# BiSheB.net
KiCad netlist of a schematic drawn in Altium Designer
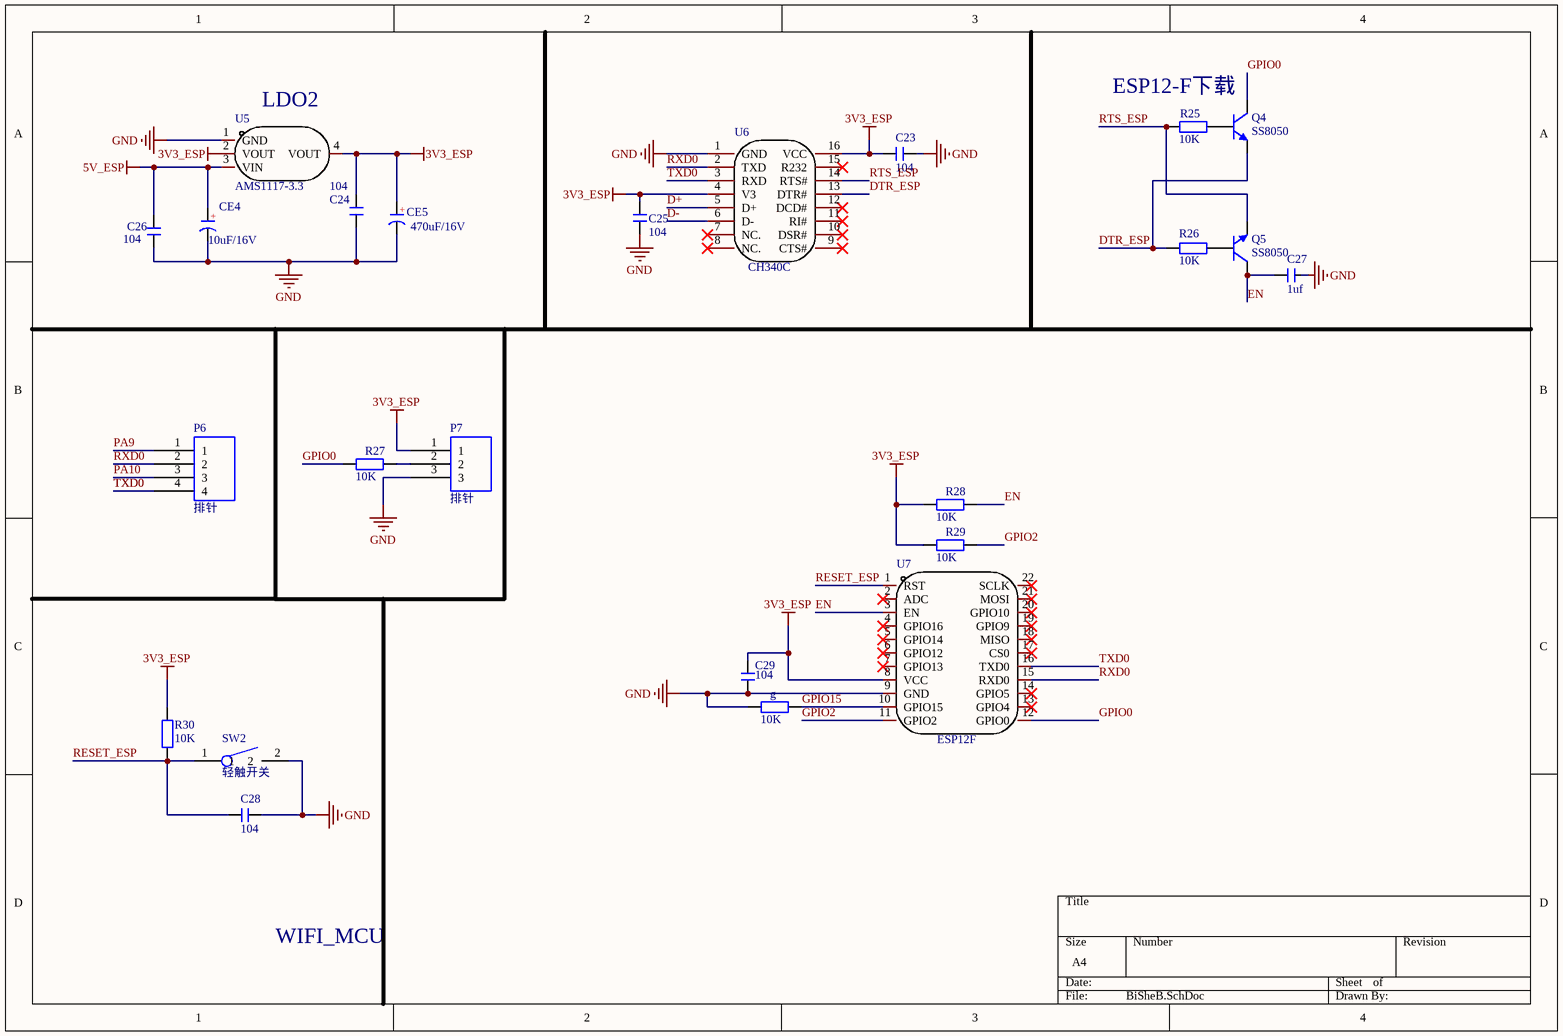
[diagram p0: BiSheB.SchDoc]

(export (version "E")
  (design (tool "Eeschema 10.0.6"))
  (components
    (comp (ref "C23")
      (value "104")
      (footprint "C 0805_L")
      (description "贴片电容")
      (libsource (lib "0.1 - 电阻-电容-电感") (part "C"))
    )
    (comp (ref "C24")
      (value "104")
      (footprint "C 0805_L")
      (description "贴片电容")
      (libsource (lib "0.1 - 电阻-电容-电感") (part "C"))
    )
    (comp (ref "C25")
      (value "104")
      (footprint "C 0805_L")
      (description "贴片电容")
      (libsource (lib "0.1 - 电阻-电容-电感") (part "C"))
    )
    (comp (ref "C26")
      (value "104")
      (footprint "C 0805_L")
      (description "贴片电容")
      (libsource (lib "0.1 - 电阻-电容-电感") (part "C"))
    )
    (comp (ref "C27")
      (value "1uf")
      (footprint "C 0805_L")
      (description "贴片电容")
      (libsource (lib "0.1 - 电阻-电容-电感") (part "C"))
    )
    (comp (ref "C28")
      (value "104")
      (footprint "C 0805_L")
      (description "贴片电容")
      (libsource (lib "0.1 - 电阻-电容-电感") (part "C"))
    )
    (comp (ref "C29")
      (value "104")
      (footprint "C 0805_L")
      (description "贴片电容")
      (libsource (lib "0.1 - 电阻-电容-电感") (part "C"))
    )
    (comp (ref "CE4")
      (value "10uF/16V")
      (footprint "CAP 1.5*4*8")
      (description "直插电解电容")
      (libsource (lib "0.1 - 电阻-电容-电感") (part "CE"))
    )
    (comp (ref "CE5")
      (value "470uF/16V")
      (footprint "CAP 3.5*8*11.5")
      (description "直插电解电容")
      (libsource (lib "0.1 - 电阻-电容-电感") (part "CE"))
    )
    (comp (ref "g")
      (value "10K")
      (footprint "R 0805_L")
      (description "贴片电阻")
      (fields (field (name "版权归属") "来自淘宝 ID：黄晶宝石"))
      (libsource (lib "0.1 - 电阻-电容-电感") (part "R"))
    )
    (comp (ref "P6")
      (value "排针")
      (footprint "4PIN")
      (description "4p排针")
      (libsource (lib "BiSheFinal") (part "4Pin"))
    )
    (comp (ref "P7")
      (value "排针")
      (footprint "3Pin")
      (description "3p排针")
      (libsource (lib "BiSheFinal") (part "3Pin"))
    )
    (comp (ref "Q4")
      (value "SS8050")
      (footprint "SOT23-3N")
      (description "高频放大-NPN型")
      (fields (field (name "版权归属") "封装库来自淘宝 ID：黄晶宝石"))
      (libsource (lib "0.4 - 三极管") (part "8050-SMD"))
    )
    (comp (ref "Q5")
      (value "SS8050")
      (footprint "SOT23-3N")
      (description "高频放大-NPN型")
      (fields (field (name "版权归属") "封装库来自淘宝 ID：黄晶宝石"))
      (libsource (lib "0.4 - 三极管") (part "8050-SMD"))
    )
    (comp (ref "R25")
      (value "10K")
      (footprint "R 0805_L")
      (description "贴片电阻")
      (fields (field (name "版权归属") "来自淘宝 ID：黄晶宝石"))
      (libsource (lib "0.1 - 电阻-电容-电感") (part "R"))
    )
    (comp (ref "R26")
      (value "10K")
      (footprint "R 0805_L")
      (description "贴片电阻")
      (fields (field (name "版权归属") "来自淘宝 ID：黄晶宝石"))
      (libsource (lib "0.1 - 电阻-电容-电感") (part "R"))
    )
    (comp (ref "R27")
      (value "10K")
      (footprint "R 0805_L")
      (description "贴片电阻")
      (fields (field (name "版权归属") "来自淘宝 ID：黄晶宝石"))
      (libsource (lib "0.1 - 电阻-电容-电感") (part "R"))
    )
    (comp (ref "R28")
      (value "10K")
      (footprint "R 0805_L")
      (description "贴片电阻")
      (fields (field (name "版权归属") "来自淘宝 ID：黄晶宝石"))
      (libsource (lib "0.1 - 电阻-电容-电感") (part "R"))
    )
    (comp (ref "R29")
      (value "10K")
      (footprint "R 0805_L")
      (description "贴片电阻")
      (fields (field (name "版权归属") "来自淘宝 ID：黄晶宝石"))
      (libsource (lib "0.1 - 电阻-电容-电感") (part "R"))
    )
    (comp (ref "R30")
      (value "10K")
      (footprint "R 0805_L")
      (description "贴片电阻")
      (fields (field (name "版权归属") "来自淘宝 ID：黄晶宝石"))
      (libsource (lib "0.1 - 电阻-电容-电感") (part "R"))
    )
    (comp (ref "SW2")
      (value "轻触开关")
      (footprint "SW1P")
      (description "单刀单掷清除开关")
      (libsource (lib "BiSheFinal") (part "SW1P"))
    )
    (comp (ref "U5")
      (value "AMS1117-3.3")
      (footprint "SOT-223-3_L6.5-W3.4-P2.30-LS7.0-BR")
      (description "输出类型:固定;输出极性:正;最大输入电压:-;输出电压:3.3V;输出电流:1A;电源纹波抑制比(PSRR):72dB@(120Hz);")
      (fields (field (name "MANUFACTURER") "AMS") (field (name "AMS1117") "AMS1117-3.3"))
      (libsource (lib "BiSheFinal") (part "AMS1117-3.3_C6186"))
    )
    (comp (ref "U6")
      (value "CH340C")
      (footprint "SOP-16_L10.0-W3.9-P1.27-LS6.0-BL")
      (description "驱动器/接收器数:-;协议类别:USB 2.0;类型:Transceiver;数据速率:2Mbps;")
      (fields (field (name "MANUFACTURER") "WCH(南京沁恒)") (field (name "CH340C") "CH340C"))
      (libsource (lib "BiSheFinal") (part "CH340C"))
    )
    (comp (ref "U7")
      (value "ESP12F")
      (footprint "WIFIM-SMD_ESP-12F-ESP8266MOD")
      (description "频率:2.4GHz;发射功率:16dBm;核心处理器:ESP8266;天线形式:PCB 板载天线;接收灵敏度:-90dBm;")
      (fields
        (field (name "MANUFACTURER") "Ai-Thinker(安信可)")
        (field (name "MANUFACTURER PART") "ESP-12F(ESP8266MOD)")
        (field (name "ESP") "ESP12F")
      )
      (libsource (lib "BiSheFinal") (part "ESP-12F(ESP8266MOD)"))
    )
  )
  (nets
    (net (code "1") (name "/D+") (class "Default")
      (node (ref "U6") (pin "5") (pinfunction "D+_5") (pintype "passive"))
    )
    (net (code "2") (name "/D-") (class "Default")
      (node (ref "U6") (pin "6") (pinfunction "D-_6") (pintype "passive"))
    )
    (net (code "3") (name "/DTR_ESP") (class "Default")
      (node (ref "Q4") (pin "2") (pinfunction "E_2") (pintype "passive"))
      (node (ref "R26") (pin "2") (pinfunction "2_2") (pintype "passive"))
      (node (ref "U6") (pin "13") (pinfunction "DTR#_13") (pintype "passive"))
    )
    (net (code "4") (name "/EN") (class "Default")
      (node (ref "C27") (pin "1") (pinfunction "1_1") (pintype "passive"))
      (node (ref "Q5") (pin "3") (pinfunction "C_3") (pintype "passive"))
      (node (ref "R28") (pin "2") (pinfunction "2_2") (pintype "passive"))
      (node (ref "U7") (pin "3") (pinfunction "EN_3") (pintype "passive"))
    )
    (net (code "5") (name "/GPIO0") (class "Default")
      (node (ref "Q4") (pin "3") (pinfunction "C_3") (pintype "passive"))
      (node (ref "R27") (pin "1") (pinfunction "1_1") (pintype "passive"))
      (node (ref "U7") (pin "12") (pinfunction "GPIO0_12") (pintype "passive"))
    )
    (net (code "6") (name "/GPIO2") (class "Default")
      (node (ref "R29") (pin "2") (pinfunction "2_2") (pintype "passive"))
      (node (ref "U7") (pin "11") (pinfunction "GPIO2_11") (pintype "passive"))
    )
    (net (code "7") (name "/GPIO15") (class "Default")
      (node (ref "U7") (pin "10") (pinfunction "GPIO15_10") (pintype "passive"))
      (node (ref "g") (pin "2") (pinfunction "2_2") (pintype "passive"))
    )
    (net (code "8") (name "/PA9") (class "Default")
      (node (ref "P6") (pin "1") (pinfunction "1_1") (pintype "passive"))
    )
    (net (code "9") (name "/PA10") (class "Default")
      (node (ref "P6") (pin "3") (pinfunction "3_3") (pintype "passive"))
    )
    (net (code "10") (name "/RESET_ESP") (class "Default")
      (node (ref "C28") (pin "1") (pinfunction "1_1") (pintype "passive"))
      (node (ref "R30") (pin "2") (pinfunction "2_2") (pintype "passive"))
      (node (ref "SW2") (pin "1") (pinfunction "1_1") (pintype "passive"))
      (node (ref "U7") (pin "1") (pinfunction "RST_1") (pintype "passive"))
    )
    (net (code "11") (name "/RTS_ESP") (class "Default")
      (node (ref "Q5") (pin "2") (pinfunction "E_2") (pintype "passive"))
      (node (ref "R25") (pin "2") (pinfunction "2_2") (pintype "passive"))
      (node (ref "U6") (pin "14") (pinfunction "RTS#_14") (pintype "passive"))
    )
    (net (code "12") (name "/RXD0") (class "Default")
      (node (ref "P6") (pin "2") (pinfunction "2_2") (pintype "passive"))
      (node (ref "U6") (pin "2") (pinfunction "TXD_2") (pintype "passive"))
      (node (ref "U7") (pin "15") (pinfunction "RXD0_15") (pintype "passive"))
    )
    (net (code "13") (name "/TXD0") (class "Default")
      (node (ref "P6") (pin "4") (pinfunction "4_4") (pintype "passive"))
      (node (ref "U6") (pin "3") (pinfunction "RXD_3") (pintype "passive"))
      (node (ref "U7") (pin "16") (pinfunction "TXD0_16") (pintype "passive"))
    )
    (net (code "14") (name "3V3_ESP") (class "Default")
      (node (ref "C23") (pin "1") (pinfunction "1_1") (pintype "passive"))
      (node (ref "C24") (pin "2") (pinfunction "2_2") (pintype "passive"))
      (node (ref "C25") (pin "2") (pinfunction "2_2") (pintype "passive"))
      (node (ref "C29") (pin "1") (pinfunction "1_1") (pintype "passive"))
      (node (ref "CE5") (pin "1") (pinfunction "A_1") (pintype "passive"))
      (node (ref "P7") (pin "1") (pinfunction "1_1") (pintype "passive"))
      (node (ref "R28") (pin "1") (pinfunction "1_1") (pintype "passive"))
      (node (ref "R29") (pin "1") (pinfunction "1_1") (pintype "passive"))
      (node (ref "R30") (pin "1") (pinfunction "1_1") (pintype "passive"))
      (node (ref "U5") (pin "2") (pinfunction "VOUT_2") (pintype "passive"))
      (node (ref "U5") (pin "4") (pinfunction "VOUT_4") (pintype "passive"))
      (node (ref "U6") (pin "16") (pinfunction "VCC_16") (pintype "passive"))
      (node (ref "U6") (pin "4") (pinfunction "V3_4") (pintype "passive"))
      (node (ref "U7") (pin "8") (pinfunction "VCC_8") (pintype "passive"))
    )
    (net (code "15") (name "5V_ESP") (class "Default")
      (node (ref "C26") (pin "1") (pinfunction "1_1") (pintype "passive"))
      (node (ref "CE4") (pin "1") (pinfunction "A_1") (pintype "passive"))
      (node (ref "U5") (pin "3") (pinfunction "VIN_3") (pintype "passive"))
    )
    (net (code "16") (name "GND") (class "Default")
      (node (ref "C23") (pin "2") (pinfunction "2_2") (pintype "passive"))
      (node (ref "C24") (pin "1") (pinfunction "1_1") (pintype "passive"))
      (node (ref "C25") (pin "1") (pinfunction "1_1") (pintype "passive"))
      (node (ref "C26") (pin "2") (pinfunction "2_2") (pintype "passive"))
      (node (ref "C27") (pin "2") (pinfunction "2_2") (pintype "passive"))
      (node (ref "C28") (pin "2") (pinfunction "2_2") (pintype "passive"))
      (node (ref "C29") (pin "2") (pinfunction "2_2") (pintype "passive"))
      (node (ref "CE4") (pin "2") (pinfunction "K_2") (pintype "passive"))
      (node (ref "CE5") (pin "2") (pinfunction "K_2") (pintype "passive"))
      (node (ref "P7") (pin "3") (pinfunction "3_3") (pintype "passive"))
      (node (ref "SW2") (pin "2") (pinfunction "2_2") (pintype "passive"))
      (node (ref "U5") (pin "1") (pinfunction "GND_1") (pintype "passive"))
      (node (ref "U6") (pin "1") (pinfunction "GND_1") (pintype "passive"))
      (node (ref "U7") (pin "9") (pinfunction "GND_9") (pintype "passive"))
      (node (ref "g") (pin "1") (pinfunction "1_1") (pintype "passive"))
    )
    (net (code "17") (name "Net-(P7-Pad2)") (class "Default")
      (node (ref "P7") (pin "2") (pinfunction "2_2") (pintype "passive"))
      (node (ref "R27") (pin "2") (pinfunction "2_2") (pintype "passive"))
    )
    (net (code "18") (name "Net-(Q4-B)") (class "Default")
      (node (ref "Q4") (pin "1") (pinfunction "B_1") (pintype "passive"))
      (node (ref "R25") (pin "1") (pinfunction "1_1") (pintype "passive"))
    )
    (net (code "19") (name "Net-(Q5-B)") (class "Default")
      (node (ref "Q5") (pin "1") (pinfunction "B_1") (pintype "passive"))
      (node (ref "R26") (pin "1") (pinfunction "1_1") (pintype "passive"))
    )
    (net (code "20") (name "unconnected-(U6-CTS#-Pad9)") (class "Default")
      (node (ref "U6") (pin "9") (pinfunction "CTS#_9") (pintype "passive+no_connect"))
    )
    (net (code "21") (name "unconnected-(U6-DCD#-Pad12)") (class "Default")
      (node (ref "U6") (pin "12") (pinfunction "DCD#_12") (pintype "passive+no_connect"))
    )
    (net (code "22") (name "unconnected-(U6-DSR#-Pad10)") (class "Default")
      (node (ref "U6") (pin "10") (pinfunction "DSR#_10") (pintype "passive+no_connect"))
    )
    (net (code "23") (name "unconnected-(U6-NC.-Pad7)") (class "Default")
      (node (ref "U6") (pin "7") (pinfunction "NC._7") (pintype "passive+no_connect"))
    )
    (net (code "24") (name "unconnected-(U6-NC.-Pad8)") (class "Default")
      (node (ref "U6") (pin "8") (pinfunction "NC._8") (pintype "passive+no_connect"))
    )
    (net (code "25") (name "unconnected-(U6-R232-Pad15)") (class "Default")
      (node (ref "U6") (pin "15") (pinfunction "R232_15") (pintype "passive+no_connect"))
    )
    (net (code "26") (name "unconnected-(U6-RI#-Pad11)") (class "Default")
      (node (ref "U6") (pin "11") (pinfunction "RI#_11") (pintype "passive+no_connect"))
    )
    (net (code "27") (name "unconnected-(U7-ADC-Pad2)") (class "Default")
      (node (ref "U7") (pin "2") (pinfunction "ADC_2") (pintype "passive+no_connect"))
    )
    (net (code "28") (name "unconnected-(U7-CS0-Pad17)") (class "Default")
      (node (ref "U7") (pin "17") (pinfunction "CS0_17") (pintype "passive+no_connect"))
    )
    (net (code "29") (name "unconnected-(U7-GPIO4-Pad13)") (class "Default")
      (node (ref "U7") (pin "13") (pinfunction "GPIO4_13") (pintype "passive+no_connect"))
    )
    (net (code "30") (name "unconnected-(U7-GPIO5-Pad14)") (class "Default")
      (node (ref "U7") (pin "14") (pinfunction "GPIO5_14") (pintype "passive+no_connect"))
    )
    (net (code "31") (name "unconnected-(U7-GPIO9-Pad19)") (class "Default")
      (node (ref "U7") (pin "19") (pinfunction "GPIO9_19") (pintype "passive+no_connect"))
    )
    (net (code "32") (name "unconnected-(U7-GPIO10-Pad20)") (class "Default")
      (node (ref "U7") (pin "20") (pinfunction "GPIO10_20") (pintype "passive+no_connect"))
    )
    (net (code "33") (name "unconnected-(U7-GPIO12-Pad6)") (class "Default")
      (node (ref "U7") (pin "6") (pinfunction "GPIO12_6") (pintype "passive+no_connect"))
    )
    (net (code "34") (name "unconnected-(U7-GPIO13-Pad7)") (class "Default")
      (node (ref "U7") (pin "7") (pinfunction "GPIO13_7") (pintype "passive+no_connect"))
    )
    (net (code "35") (name "unconnected-(U7-GPIO14-Pad5)") (class "Default")
      (node (ref "U7") (pin "5") (pinfunction "GPIO14_5") (pintype "passive+no_connect"))
    )
    (net (code "36") (name "unconnected-(U7-GPIO16-Pad4)") (class "Default")
      (node (ref "U7") (pin "4") (pinfunction "GPIO16_4") (pintype "passive+no_connect"))
    )
    (net (code "37") (name "unconnected-(U7-MISO-Pad18)") (class "Default")
      (node (ref "U7") (pin "18") (pinfunction "MISO_18") (pintype "passive+no_connect"))
    )
    (net (code "38") (name "unconnected-(U7-MOSI-Pad21)") (class "Default")
      (node (ref "U7") (pin "21") (pinfunction "MOSI_21") (pintype "passive+no_connect"))
    )
    (net (code "39") (name "unconnected-(U7-SCLK-Pad22)") (class "Default")
      (node (ref "U7") (pin "22") (pinfunction "SCLK_22") (pintype "passive+no_connect"))
    )
  )
)
